# ACS712.net
KiCad netlist of a schematic drawn in Altium Designer
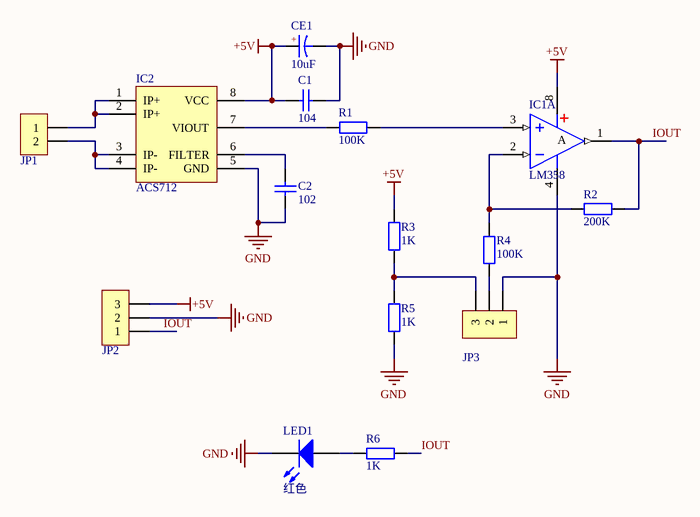
[diagram p0: ACS712电流检测.SchDoc]

(export (version "E")
  (design (tool "Eeschema 10.0.6"))
  (components
    (comp (ref "C1")
      (value "104")
      (footprint "CC 2.2*5")
      (description "瓷片电容")
      (libsource (lib "0.1 - 电阻-电容-电感-磁珠-电位器") (part "CC"))
    )
    (comp (ref "C2")
      (value "102")
      (footprint "CC 1.8*3.6")
      (description "瓷片电容")
      (libsource (lib "0.1 - 电阻-电容-电感-磁珠-电位器") (part "CC"))
    )
    (comp (ref "CE1")
      (value "10uF")
      (footprint "CAP 2.5*5*11 - BK")
      (description "直插电解电容")
      (libsource (lib "0.1 - 电阻-电容-电感-磁珠-电位器") (part "CE"))
    )
    (comp (ref "IC1")
      (value "LM358")
      (footprint "DIP8-300_MH")
      (description "双路运放")
      (libsource (lib "1.0 - 常见芯片") (part "LM358"))
    )
    (comp (ref "IC2")
      (value "ACS712")
      (footprint "SOP8_M")
      (description "电流检测芯片")
      (libsource (lib "1.0 - 常见芯片") (part "ACS712"))
    )
    (comp (ref "JP1")
      (value "HDR-1X2")
      (footprint "KF7620-2P")
      (description "2P接插件")
      (libsource (lib "6.2 - 接插件-脚距7.62 (300mil) ") (part "Header 2"))
    )
    (comp (ref "JP2")
      (value "HDR-1X3")
      (footprint "KF128-3.81-3P")
      (description "3P接插件")
      (libsource (lib "5.7 - 接插件-脚距3.81 (150mil) ") (part "Header 3"))
    )
    (comp (ref "JP3")
      (value "HDR-1X3")
      (footprint "HDR2.54-LI-3P")
      (description "3P接插件")
      (libsource (lib "5.5 - 接插件-脚距2.54 (100mil) ") (part "Header 3"))
    )
    (comp (ref "LED1")
      (value "红色")
      (footprint "LED 3MM-B")
      (description "直插3mm LED")
      (libsource (lib "0.3 - LED发光二极管") (part "LED-3MM"))
    )
    (comp (ref "R1")
      (value "100K")
      (footprint "RS 1/4W")
      (description "色环电阻")
      (libsource (lib "0.1 - 电阻-电容-电感-磁珠-电位器") (part "R-S"))
    )
    (comp (ref "R2")
      (value "200K")
      (footprint "RS 1/4W")
      (description "色环电阻")
      (libsource (lib "0.1 - 电阻-电容-电感-磁珠-电位器") (part "R-S"))
    )
    (comp (ref "R3")
      (value "1K")
      (footprint "RS 1/4W")
      (description "色环电阻")
      (libsource (lib "0.1 - 电阻-电容-电感-磁珠-电位器") (part "R-S"))
    )
    (comp (ref "R4")
      (value "100K")
      (footprint "RS 1/4W")
      (description "色环电阻")
      (libsource (lib "0.1 - 电阻-电容-电感-磁珠-电位器") (part "R-S"))
    )
    (comp (ref "R5")
      (value "1K")
      (footprint "RS 1/4W")
      (description "色环电阻")
      (libsource (lib "0.1 - 电阻-电容-电感-磁珠-电位器") (part "R-S"))
    )
    (comp (ref "R6")
      (value "1K")
      (footprint "RS 1/4W")
      (description "色环电阻")
      (libsource (lib "0.1 - 电阻-电容-电感-磁珠-电位器") (part "R-S"))
    )
  )
  (nets
    (net (code "1") (name "+5V") (class "Default")
      (node (ref "C1") (pin "1") (pinfunction "1_1") (pintype "passive"))
      (node (ref "CE1") (pin "1") (pinfunction "1_1") (pintype "passive"))
      (node (ref "IC1") (pin "8") (pinfunction "V+_8") (pintype "power_in"))
      (node (ref "IC2") (pin "8") (pinfunction "VCC_8") (pintype "passive"))
      (node (ref "JP2") (pin "3") (pinfunction "3_3") (pintype "passive"))
      (node (ref "R3") (pin "2") (pinfunction "2_2") (pintype "passive"))
    )
    (net (code "2") (name "/IOUT") (class "Default")
      (node (ref "IC1") (pin "1") (pinfunction "OUT_1") (pintype "output"))
      (node (ref "JP2") (pin "1") (pinfunction "1_1") (pintype "passive"))
      (node (ref "R2") (pin "2") (pinfunction "2_2") (pintype "passive"))
      (node (ref "R6") (pin "1") (pinfunction "1_1") (pintype "passive"))
    )
    (net (code "3") (name "GND") (class "Default")
      (node (ref "C1") (pin "2") (pinfunction "2_2") (pintype "passive"))
      (node (ref "C2") (pin "1") (pinfunction "1_1") (pintype "passive"))
      (node (ref "CE1") (pin "2") (pinfunction "2_2") (pintype "passive"))
      (node (ref "IC1") (pin "4") (pinfunction "V-_4") (pintype "power_in"))
      (node (ref "IC2") (pin "5") (pinfunction "GND_5") (pintype "passive"))
      (node (ref "JP2") (pin "2") (pinfunction "2_2") (pintype "passive"))
      (node (ref "JP3") (pin "1") (pinfunction "1_1") (pintype "passive"))
      (node (ref "LED1") (pin "2") (pinfunction "K_2") (pintype "passive"))
      (node (ref "R5") (pin "1") (pinfunction "1_1") (pintype "passive"))
    )
    (net (code "4") (name "Net-(IC1A-IN+)") (class "Default")
      (node (ref "IC1") (pin "3") (pinfunction "IN+_3") (pintype "input"))
      (node (ref "R1") (pin "2") (pinfunction "2_2") (pintype "passive"))
    )
    (net (code "5") (name "Net-(IC1A-IN-)") (class "Default")
      (node (ref "IC1") (pin "2") (pinfunction "IN-_2") (pintype "input"))
      (node (ref "R2") (pin "1") (pinfunction "1_1") (pintype "passive"))
      (node (ref "R4") (pin "2") (pinfunction "2_2") (pintype "passive"))
    )
    (net (code "6") (name "Net-(IC2-FILTER)") (class "Default")
      (node (ref "C2") (pin "2") (pinfunction "2_2") (pintype "passive"))
      (node (ref "IC2") (pin "6") (pinfunction "FILTER_6") (pintype "passive"))
    )
    (net (code "7") (name "Net-(IC2-IP+-Pad1)") (class "Default")
      (node (ref "IC2") (pin "1") (pinfunction "IP+_1") (pintype "passive"))
      (node (ref "IC2") (pin "2") (pinfunction "IP+_2") (pintype "passive"))
      (node (ref "JP1") (pin "1") (pinfunction "1_1") (pintype "passive"))
    )
    (net (code "8") (name "Net-(IC2-IP--Pad3)") (class "Default")
      (node (ref "IC2") (pin "3") (pinfunction "IP-_3") (pintype "passive"))
      (node (ref "IC2") (pin "4") (pinfunction "IP-_4") (pintype "passive"))
      (node (ref "JP1") (pin "2") (pinfunction "2_2") (pintype "passive"))
    )
    (net (code "9") (name "Net-(IC2-VIOUT)") (class "Default")
      (node (ref "IC2") (pin "7") (pinfunction "VIOUT_7") (pintype "passive"))
      (node (ref "R1") (pin "1") (pinfunction "1_1") (pintype "passive"))
    )
    (net (code "10") (name "Net-(JP3-Pad2)") (class "Default")
      (node (ref "JP3") (pin "2") (pinfunction "2_2") (pintype "passive"))
      (node (ref "R4") (pin "1") (pinfunction "1_1") (pintype "passive"))
    )
    (net (code "11") (name "Net-(JP3-Pad3)") (class "Default")
      (node (ref "JP3") (pin "3") (pinfunction "3_3") (pintype "passive"))
      (node (ref "R3") (pin "1") (pinfunction "1_1") (pintype "passive"))
      (node (ref "R5") (pin "2") (pinfunction "2_2") (pintype "passive"))
    )
    (net (code "12") (name "Net-(LED1-A)") (class "Default")
      (node (ref "LED1") (pin "1") (pinfunction "A_1") (pintype "passive"))
      (node (ref "R6") (pin "2") (pinfunction "2_2") (pintype "passive"))
    )
  )
)
